# PCB_DYBoard_Bandmaster_V2_SCH4.net
KiCad netlist of a schematic drawn in Altium Designer
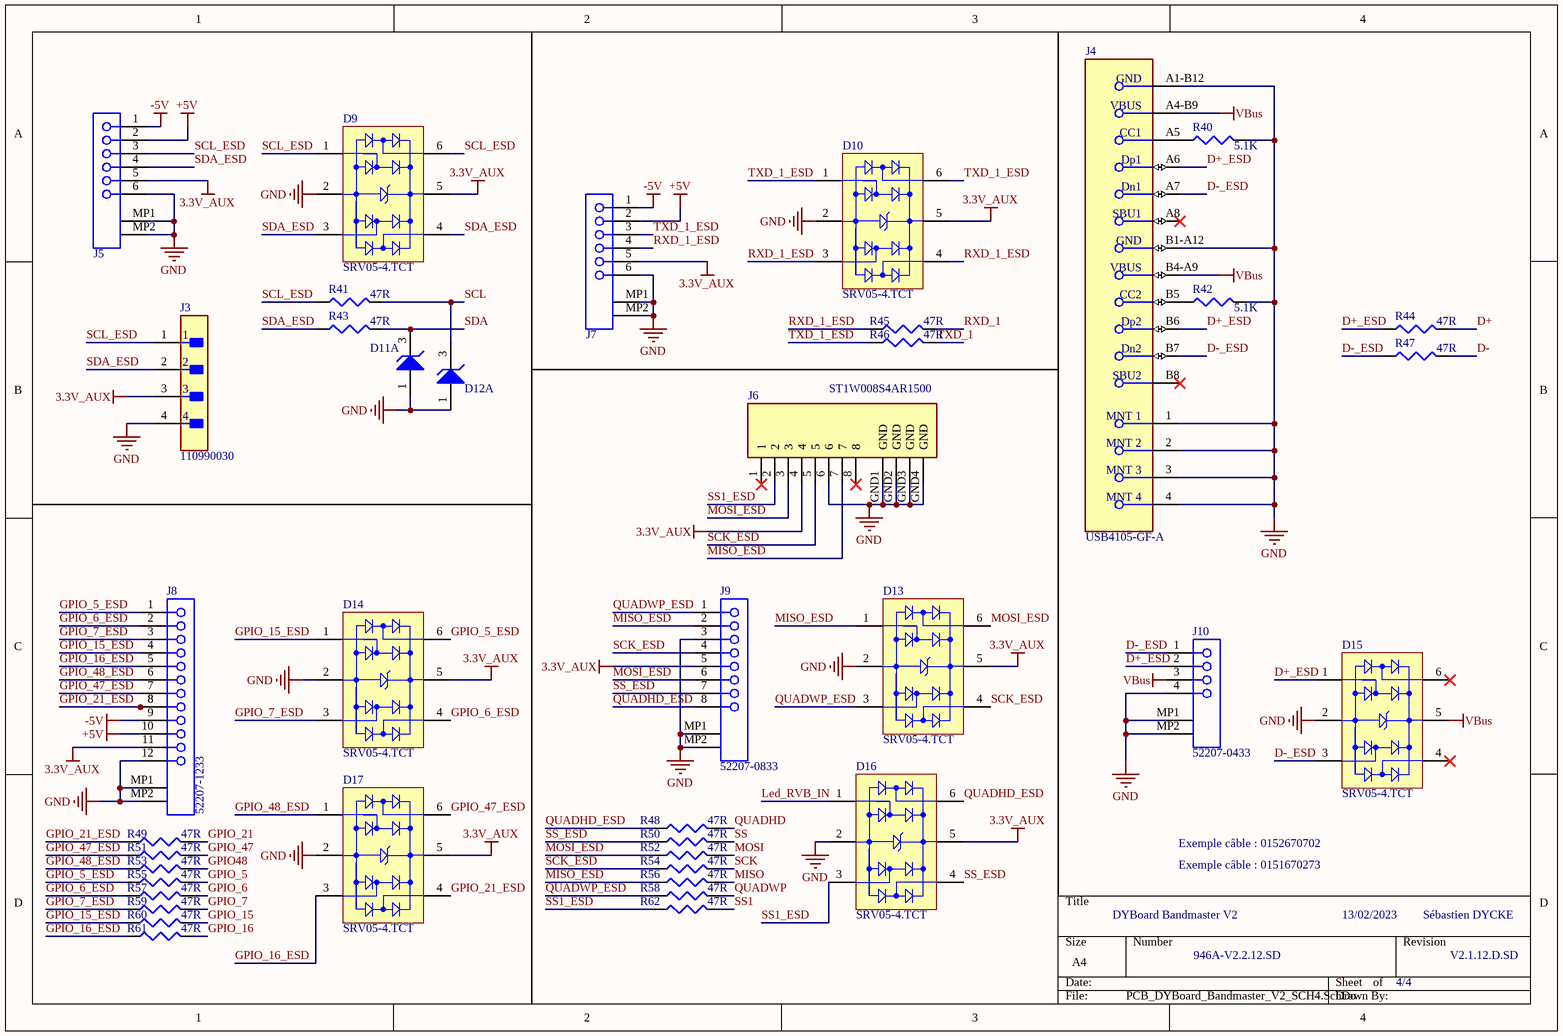
[diagram p0: PCB_DYBoard_Bandmaster_V2_SCH4.SchDoc]

(export (version "E")
  (design (tool "Eeschema 10.0.6"))
  (components
    (comp (ref "D9")
      (value "SRV05-4.TCT")
      (footprint "SMTC-SOT23-6_V")
      (fields (field (name "MANUFACTURER") "Semtech"))
      (libsource (lib "Altium Content Vault") (part "STM-USB_DVI_HDMIULC6-4SC6X-SOT23-6L"))
    )
    (comp (ref "D10")
      (value "SRV05-4.TCT")
      (footprint "SMTC-SOT23-6_V")
      (fields (field (name "MANUFACTURER") "Semtech"))
      (libsource (lib "Altium Content Vault") (part "STM-USB_DVI_HDMIULC6-4SC6X-SOT23-6L"))
    )
    (comp (ref "D11")
      (value "BZX84C3V9LT1G")
      (footprint "ONSC-SOT-23-3-318-08_V")
      (description "Zener Voltage Regulator, 225 mW, 3-Pin SOT-23, Pb-Free, Tape and Reel")
      (fields (field (name "MANUFACTURER") "On Semiconductor"))
      (libsource (lib "Altium Content Vault") (part "ONSC-A1K3-3"))
    )
    (comp (ref "D12")
      (value "BZX84C3V9LT1G")
      (footprint "ONSC-SOT-23-3-318-08_V")
      (description "Zener Voltage Regulator, 225 mW, 3-Pin SOT-23, Pb-Free, Tape and Reel")
      (fields (field (name "MANUFACTURER") "On Semiconductor"))
      (libsource (lib "Altium Content Vault") (part "ONSC-A1K3-3"))
    )
    (comp (ref "D13")
      (value "SRV05-4.TCT")
      (footprint "SMTC-SOT23-6_V")
      (fields (field (name "MANUFACTURER") "Semtech"))
      (libsource (lib "Altium Content Vault") (part "STM-USB_DVI_HDMIULC6-4SC6X-SOT23-6L"))
    )
    (comp (ref "D14")
      (value "SRV05-4.TCT")
      (footprint "SMTC-SOT23-6_V")
      (fields (field (name "MANUFACTURER") "Semtech"))
      (libsource (lib "Altium Content Vault") (part "STM-USB_DVI_HDMIULC6-4SC6X-SOT23-6L"))
    )
    (comp (ref "D15")
      (value "SRV05-4.TCT")
      (footprint "SMTC-SOT23-6_V")
      (fields (field (name "MANUFACTURER") "Semtech"))
      (libsource (lib "Altium Content Vault") (part "STM-USB_DVI_HDMIULC6-4SC6X-SOT23-6L"))
    )
    (comp (ref "D16")
      (value "SRV05-4.TCT")
      (footprint "SMTC-SOT23-6_V")
      (fields (field (name "MANUFACTURER") "Semtech"))
      (libsource (lib "Altium Content Vault") (part "STM-USB_DVI_HDMIULC6-4SC6X-SOT23-6L"))
    )
    (comp (ref "D17")
      (value "SRV05-4.TCT")
      (footprint "SMTC-SOT23-6_V")
      (fields (field (name "MANUFACTURER") "Semtech"))
      (libsource (lib "Altium Content Vault") (part "STM-USB_DVI_HDMIULC6-4SC6X-SOT23-6L"))
    )
    (comp (ref "J3")
      (value "110990030")
      (footprint "FP-110990030-MFG")
      (description "GROVE 2MM 4PIN VERT CONN 10PCS")
      (libsource (lib "Altium Content Vault") (part "299a8cea1bdcbc3624fe62c390fa72c"))
    )
    (comp (ref "J4")
      (value "USB4105-GF-A")
      (footprint "FP-USB4105-GF-A-MFG")
      (description "CONN RCPT USB2.0 TYPEC 5A")
      (fields
        (field (name "MANUFACTURER") "GCT")
        (field (name "OCTOPART") "https://octopart.com/usb4105-gf-a-gct-106627878")
      )
      (libsource (lib "Altium Content Vault") (part "e7c17a616881a82b79941196b4bec10"))
    )
    (comp (ref "J5")
      (value "SEB_MOLeX_6p")
      (footprint "SEB_MOLeX_6p")
      (libsource (lib "Lib_Altium_Sebastien_DYCKE") (part "SEB_MOLeX_6p"))
    )
    (comp (ref "J6")
      (value "ST1W008S4AR1500")
      (footprint "JAE_ST1W008S4AR1500")
      (description "8 Position Card Connector Secure Digital - microSDâ„¢ Surface Mount, Right Angle Gold")
      (fields (field (name "MF") "JAE Electronics"))
      (libsource (lib "ST1W008S4AR1500") (part "ST1W008S4AR1500"))
    )
    (comp (ref "J7")
      (value "SEB_MOLeX_6p")
      (footprint "SEB_MOLeX_6p")
      (libsource (lib "Lib_Altium_Sebastien_DYCKE") (part "SEB_MOLeX_6p"))
    )
    (comp (ref "J8")
      (value "52207-1233")
      (footprint "52207-1233")
      (libsource (lib "Lib_Altium_Sebastien_DYCKE") (part "52207-1233"))
    )
    (comp (ref "J9")
      (value "52207-0833")
      (footprint "con_molex_8_52207-0833")
      (libsource (lib "Lib_Altium_Sebastien_DYCKE") (part "52207-0833"))
    )
    (comp (ref "J10")
      (value "52207-0433")
      (footprint "52207-0433")
      (libsource (lib "Lib_Altium_Sebastien_DYCKE") (part "52207-0433"))
    )
    (comp (ref "R40")
      (value "5.1K")
      (footprint "J1-0603")
      (description "Resistor")
      (fields (field (name "Comment") "Res3") (field (name "PUBLISHER") "Altium Limited"))
      (libsource (lib "Miscellaneous Devices") (part "Res3"))
    )
    (comp (ref "R41")
      (value "47R")
      (footprint "J1-0603")
      (description "Resistor")
      (fields (field (name "Comment") "Res3") (field (name "PUBLISHER") "Altium Limited"))
      (libsource (lib "Miscellaneous Devices") (part "Res3"))
    )
    (comp (ref "R42")
      (value "5.1K")
      (footprint "J1-0603")
      (description "Resistor")
      (fields (field (name "Comment") "Res3") (field (name "PUBLISHER") "Altium Limited"))
      (libsource (lib "Miscellaneous Devices") (part "Res3"))
    )
    (comp (ref "R43")
      (value "47R")
      (footprint "J1-0603")
      (description "Resistor")
      (fields (field (name "Comment") "Res3") (field (name "PUBLISHER") "Altium Limited"))
      (libsource (lib "Miscellaneous Devices") (part "Res3"))
    )
    (comp (ref "R44")
      (value "47R")
      (footprint "J1-0603")
      (description "Resistor")
      (fields (field (name "Comment") "Res3") (field (name "PUBLISHER") "Altium Limited"))
      (libsource (lib "Miscellaneous Devices") (part "Res3"))
    )
    (comp (ref "R45")
      (value "47R")
      (footprint "J1-0603")
      (description "Resistor")
      (fields (field (name "Comment") "Res3") (field (name "PUBLISHER") "Altium Limited"))
      (libsource (lib "Miscellaneous Devices") (part "Res3"))
    )
    (comp (ref "R46")
      (value "47R")
      (footprint "J1-0603")
      (description "Resistor")
      (fields (field (name "Comment") "Res3") (field (name "PUBLISHER") "Altium Limited"))
      (libsource (lib "Miscellaneous Devices") (part "Res3"))
    )
    (comp (ref "R47")
      (value "47R")
      (footprint "J1-0603")
      (description "Resistor")
      (fields (field (name "Comment") "Res3") (field (name "PUBLISHER") "Altium Limited"))
      (libsource (lib "Miscellaneous Devices") (part "Res3"))
    )
    (comp (ref "R48")
      (value "47R")
      (footprint "J1-0603")
      (description "Resistor")
      (fields (field (name "Comment") "Res3") (field (name "PUBLISHER") "Altium Limited"))
      (libsource (lib "Miscellaneous Devices") (part "Res3"))
    )
    (comp (ref "R49")
      (value "47R")
      (footprint "J1-0603")
      (description "Resistor")
      (fields (field (name "Comment") "Res3") (field (name "PUBLISHER") "Altium Limited"))
      (libsource (lib "Miscellaneous Devices") (part "Res3"))
    )
    (comp (ref "R50")
      (value "47R")
      (footprint "J1-0603")
      (description "Resistor")
      (fields (field (name "Comment") "Res3") (field (name "PUBLISHER") "Altium Limited"))
      (libsource (lib "Miscellaneous Devices") (part "Res3"))
    )
    (comp (ref "R51")
      (value "47R")
      (footprint "J1-0603")
      (description "Resistor")
      (fields (field (name "Comment") "Res3") (field (name "PUBLISHER") "Altium Limited"))
      (libsource (lib "Miscellaneous Devices") (part "Res3"))
    )
    (comp (ref "R52")
      (value "47R")
      (footprint "J1-0603")
      (description "Resistor")
      (fields (field (name "Comment") "Res3") (field (name "PUBLISHER") "Altium Limited"))
      (libsource (lib "Miscellaneous Devices") (part "Res3"))
    )
    (comp (ref "R53")
      (value "47R")
      (footprint "J1-0603")
      (description "Resistor")
      (fields (field (name "Comment") "Res3") (field (name "PUBLISHER") "Altium Limited"))
      (libsource (lib "Miscellaneous Devices") (part "Res3"))
    )
    (comp (ref "R54")
      (value "47R")
      (footprint "J1-0603")
      (description "Resistor")
      (fields (field (name "Comment") "Res3") (field (name "PUBLISHER") "Altium Limited"))
      (libsource (lib "Miscellaneous Devices") (part "Res3"))
    )
    (comp (ref "R55")
      (value "47R")
      (footprint "J1-0603")
      (description "Resistor")
      (fields (field (name "Comment") "Res3") (field (name "PUBLISHER") "Altium Limited"))
      (libsource (lib "Miscellaneous Devices") (part "Res3"))
    )
    (comp (ref "R56")
      (value "47R")
      (footprint "J1-0603")
      (description "Resistor")
      (fields (field (name "Comment") "Res3") (field (name "PUBLISHER") "Altium Limited"))
      (libsource (lib "Miscellaneous Devices") (part "Res3"))
    )
    (comp (ref "R57")
      (value "47R")
      (footprint "J1-0603")
      (description "Resistor")
      (fields (field (name "Comment") "Res3") (field (name "PUBLISHER") "Altium Limited"))
      (libsource (lib "Miscellaneous Devices") (part "Res3"))
    )
    (comp (ref "R58")
      (value "47R")
      (footprint "J1-0603")
      (description "Resistor")
      (fields (field (name "Comment") "Res3") (field (name "PUBLISHER") "Altium Limited"))
      (libsource (lib "Miscellaneous Devices") (part "Res3"))
    )
    (comp (ref "R59")
      (value "47R")
      (footprint "J1-0603")
      (description "Resistor")
      (fields (field (name "Comment") "Res3") (field (name "PUBLISHER") "Altium Limited"))
      (libsource (lib "Miscellaneous Devices") (part "Res3"))
    )
    (comp (ref "R60")
      (value "47R")
      (footprint "J1-0603")
      (description "Resistor")
      (fields (field (name "Comment") "Res3") (field (name "PUBLISHER") "Altium Limited"))
      (libsource (lib "Miscellaneous Devices") (part "Res3"))
    )
    (comp (ref "R61")
      (value "47R")
      (footprint "J1-0603")
      (description "Resistor")
      (fields (field (name "Comment") "Res3") (field (name "PUBLISHER") "Altium Limited"))
      (libsource (lib "Miscellaneous Devices") (part "Res3"))
    )
    (comp (ref "R62")
      (value "47R")
      (footprint "J1-0603")
      (description "Resistor")
      (fields (field (name "Comment") "Res3") (field (name "PUBLISHER") "Altium Limited"))
      (libsource (lib "Miscellaneous Devices") (part "Res3"))
    )
  )
  (nets
    (net (code "1") (name "+5V") (class "Default")
      (node (ref "J5") (pin "2") (pinfunction "2_2") (pintype "passive"))
      (node (ref "J7") (pin "2") (pinfunction "2_2") (pintype "passive"))
      (node (ref "J8") (pin "10") (pinfunction "10_10") (pintype "passive"))
    )
    (net (code "2") (name "-5V") (class "Default")
      (node (ref "J5") (pin "1") (pinfunction "1_1") (pintype "passive"))
      (node (ref "J7") (pin "1") (pinfunction "1_1") (pintype "passive"))
      (node (ref "J8") (pin "9") (pinfunction "9_9") (pintype "passive"))
    )
    (net (code "3") (name "/D+") (class "Default")
      (node (ref "R44") (pin "2") (pinfunction "2_2") (pintype "passive"))
    )
    (net (code "4") (name "/D+_ESD") (class "Default")
      (node (ref "D15") (pin "1") (pinfunction "I/O_1_1") (pintype "passive"))
      (node (ref "J10") (pin "2") (pinfunction "2_2") (pintype "passive"))
      (node (ref "J4") (pin "A6") (pinfunction "Dp1_A6") (pintype "bidirectional"))
      (node (ref "J4") (pin "B6") (pinfunction "Dp2_B6") (pintype "bidirectional"))
      (node (ref "R44") (pin "1") (pinfunction "1_1") (pintype "passive"))
    )
    (net (code "5") (name "/D-") (class "Default")
      (node (ref "R47") (pin "2") (pinfunction "2_2") (pintype "passive"))
    )
    (net (code "6") (name "/D-_ESD") (class "Default")
      (node (ref "D15") (pin "3") (pinfunction "I/O_2_3") (pintype "passive"))
      (node (ref "J10") (pin "1") (pinfunction "1_1") (pintype "passive"))
      (node (ref "J4") (pin "A7") (pinfunction "Dn1_A7") (pintype "bidirectional"))
      (node (ref "J4") (pin "B7") (pinfunction "Dn2_B7") (pintype "bidirectional"))
      (node (ref "R47") (pin "1") (pinfunction "1_1") (pintype "passive"))
    )
    (net (code "7") (name "/GPIO48") (class "Default")
      (node (ref "R53") (pin "2") (pinfunction "2_2") (pintype "passive"))
    )
    (net (code "8") (name "/GPIO_5") (class "Default")
      (node (ref "R55") (pin "2") (pinfunction "2_2") (pintype "passive"))
    )
    (net (code "9") (name "/GPIO_5_ESD") (class "Default")
      (node (ref "D14") (pin "6") (pinfunction "I/O_4_6") (pintype "passive"))
      (node (ref "J8") (pin "1") (pinfunction "1_1") (pintype "passive"))
      (node (ref "R55") (pin "1") (pinfunction "1_1") (pintype "passive"))
    )
    (net (code "10") (name "/GPIO_6") (class "Default")
      (node (ref "R57") (pin "2") (pinfunction "2_2") (pintype "passive"))
    )
    (net (code "11") (name "/GPIO_6_ESD") (class "Default")
      (node (ref "D14") (pin "4") (pinfunction "I/O_3_4") (pintype "passive"))
      (node (ref "J8") (pin "2") (pinfunction "2_2") (pintype "passive"))
      (node (ref "R57") (pin "1") (pinfunction "1_1") (pintype "passive"))
    )
    (net (code "12") (name "/GPIO_7") (class "Default")
      (node (ref "R59") (pin "2") (pinfunction "2_2") (pintype "passive"))
    )
    (net (code "13") (name "/GPIO_7_ESD") (class "Default")
      (node (ref "D14") (pin "3") (pinfunction "I/O_2_3") (pintype "passive"))
      (node (ref "J8") (pin "3") (pinfunction "3_3") (pintype "passive"))
      (node (ref "R59") (pin "1") (pinfunction "1_1") (pintype "passive"))
    )
    (net (code "14") (name "/GPIO_15") (class "Default")
      (node (ref "R60") (pin "2") (pinfunction "2_2") (pintype "passive"))
    )
    (net (code "15") (name "/GPIO_15_ESD") (class "Default")
      (node (ref "D14") (pin "1") (pinfunction "I/O_1_1") (pintype "passive"))
      (node (ref "J8") (pin "4") (pinfunction "4_4") (pintype "passive"))
      (node (ref "R60") (pin "1") (pinfunction "1_1") (pintype "passive"))
    )
    (net (code "16") (name "/GPIO_16") (class "Default")
      (node (ref "R61") (pin "2") (pinfunction "2_2") (pintype "passive"))
    )
    (net (code "17") (name "/GPIO_16_ESD") (class "Default")
      (node (ref "D17") (pin "3") (pinfunction "I/O_2_3") (pintype "passive"))
      (node (ref "J8") (pin "5") (pinfunction "5_5") (pintype "passive"))
      (node (ref "R61") (pin "1") (pinfunction "1_1") (pintype "passive"))
    )
    (net (code "18") (name "/GPIO_21") (class "Default")
      (node (ref "R49") (pin "2") (pinfunction "2_2") (pintype "passive"))
    )
    (net (code "19") (name "/GPIO_21_ESD") (class "Default")
      (node (ref "D17") (pin "4") (pinfunction "I/O_3_4") (pintype "passive"))
      (node (ref "J8") (pin "8") (pinfunction "8_8") (pintype "passive"))
      (node (ref "R49") (pin "1") (pinfunction "1_1") (pintype "passive"))
    )
    (net (code "20") (name "/GPIO_47") (class "Default")
      (node (ref "R51") (pin "2") (pinfunction "2_2") (pintype "passive"))
    )
    (net (code "21") (name "/GPIO_47_ESD") (class "Default")
      (node (ref "D17") (pin "6") (pinfunction "I/O_4_6") (pintype "passive"))
      (node (ref "J8") (pin "7") (pinfunction "7_7") (pintype "passive"))
      (node (ref "R51") (pin "1") (pinfunction "1_1") (pintype "passive"))
    )
    (net (code "22") (name "/GPIO_48_ESD") (class "Default")
      (node (ref "D17") (pin "1") (pinfunction "I/O_1_1") (pintype "passive"))
      (node (ref "J8") (pin "6") (pinfunction "6_6") (pintype "passive"))
      (node (ref "R53") (pin "1") (pinfunction "1_1") (pintype "passive"))
    )
    (net (code "23") (name "/Led_RVB_IN") (class "Default")
      (node (ref "D16") (pin "1") (pinfunction "I/O_1_1") (pintype "passive"))
    )
    (net (code "24") (name "/MISO") (class "Default")
      (node (ref "R56") (pin "2") (pinfunction "2_2") (pintype "passive"))
    )
    (net (code "25") (name "/MISO_ESD") (class "Default")
      (node (ref "D13") (pin "1") (pinfunction "I/O_1_1") (pintype "passive"))
      (node (ref "J6") (pin "7") (pinfunction "7_7") (pintype "passive"))
      (node (ref "J9") (pin "2") (pinfunction "2_2") (pintype "passive"))
      (node (ref "R56") (pin "1") (pinfunction "1_1") (pintype "passive"))
    )
    (net (code "26") (name "/MOSI") (class "Default")
      (node (ref "R52") (pin "2") (pinfunction "2_2") (pintype "passive"))
    )
    (net (code "27") (name "/MOSI_ESD") (class "Default")
      (node (ref "D13") (pin "6") (pinfunction "I/O_4_6") (pintype "passive"))
      (node (ref "J6") (pin "3") (pinfunction "3_3") (pintype "passive"))
      (node (ref "J9") (pin "6") (pinfunction "6_6") (pintype "passive"))
      (node (ref "R52") (pin "1") (pinfunction "1_1") (pintype "passive"))
    )
    (net (code "28") (name "/QUADHD") (class "Default")
      (node (ref "R48") (pin "2") (pinfunction "2_2") (pintype "passive"))
    )
    (net (code "29") (name "/QUADHD_ESD") (class "Default")
      (node (ref "D16") (pin "6") (pinfunction "I/O_4_6") (pintype "passive"))
      (node (ref "J9") (pin "8") (pinfunction "8_8") (pintype "passive"))
      (node (ref "R48") (pin "1") (pinfunction "1_1") (pintype "passive"))
    )
    (net (code "30") (name "/QUADWP") (class "Default")
      (node (ref "R58") (pin "2") (pinfunction "2_2") (pintype "passive"))
    )
    (net (code "31") (name "/QUADWP_ESD") (class "Default")
      (node (ref "D13") (pin "3") (pinfunction "I/O_2_3") (pintype "passive"))
      (node (ref "J9") (pin "1") (pinfunction "1_1") (pintype "passive"))
      (node (ref "R58") (pin "1") (pinfunction "1_1") (pintype "passive"))
    )
    (net (code "32") (name "/RXD_1") (class "Default")
      (node (ref "R45") (pin "2") (pinfunction "2_2") (pintype "passive"))
    )
    (net (code "33") (name "/RXD_1_ESD") (class "Default")
      (node (ref "D10") (pin "3") (pinfunction "I/O_2_3") (pintype "passive"))
      (node (ref "D10") (pin "4") (pinfunction "I/O_3_4") (pintype "passive"))
      (node (ref "J7") (pin "4") (pinfunction "4_4") (pintype "passive"))
      (node (ref "R45") (pin "1") (pinfunction "1_1") (pintype "passive"))
    )
    (net (code "34") (name "/SCK") (class "Default")
      (node (ref "R54") (pin "2") (pinfunction "2_2") (pintype "passive"))
    )
    (net (code "35") (name "/SCK_ESD") (class "Default")
      (node (ref "D13") (pin "4") (pinfunction "I/O_3_4") (pintype "passive"))
      (node (ref "J6") (pin "5") (pinfunction "5_5") (pintype "passive"))
      (node (ref "J9") (pin "4") (pinfunction "4_4") (pintype "passive"))
      (node (ref "R54") (pin "1") (pinfunction "1_1") (pintype "passive"))
    )
    (net (code "36") (name "/SCL") (class "Default")
      (node (ref "D12") (pin "3") (pinfunction "K_3") (pintype "passive"))
      (node (ref "R41") (pin "2") (pinfunction "2_2") (pintype "passive"))
    )
    (net (code "37") (name "/SCL_ESD") (class "Default")
      (node (ref "D9") (pin "1") (pinfunction "I/O_1_1") (pintype "passive"))
      (node (ref "D9") (pin "6") (pinfunction "I/O_4_6") (pintype "passive"))
      (node (ref "J3") (pin "1") (pinfunction "1_1") (pintype "passive"))
      (node (ref "J5") (pin "3") (pinfunction "3_3") (pintype "passive"))
      (node (ref "R41") (pin "1") (pinfunction "1_1") (pintype "passive"))
    )
    (net (code "38") (name "/SDA") (class "Default")
      (node (ref "D11") (pin "3") (pinfunction "K_3") (pintype "passive"))
      (node (ref "R43") (pin "2") (pinfunction "2_2") (pintype "passive"))
    )
    (net (code "39") (name "/SDA_ESD") (class "Default")
      (node (ref "D9") (pin "3") (pinfunction "I/O_2_3") (pintype "passive"))
      (node (ref "D9") (pin "4") (pinfunction "I/O_3_4") (pintype "passive"))
      (node (ref "J3") (pin "2") (pinfunction "2_2") (pintype "passive"))
      (node (ref "J5") (pin "4") (pinfunction "4_4") (pintype "passive"))
      (node (ref "R43") (pin "1") (pinfunction "1_1") (pintype "passive"))
    )
    (net (code "40") (name "/SS") (class "Default")
      (node (ref "R50") (pin "2") (pinfunction "2_2") (pintype "passive"))
    )
    (net (code "41") (name "/SS1") (class "Default")
      (node (ref "R62") (pin "2") (pinfunction "2_2") (pintype "passive"))
    )
    (net (code "42") (name "/SS1_ESD") (class "Default")
      (node (ref "D16") (pin "3") (pinfunction "I/O_2_3") (pintype "passive"))
      (node (ref "J6") (pin "2") (pinfunction "2_2") (pintype "passive"))
      (node (ref "R62") (pin "1") (pinfunction "1_1") (pintype "passive"))
    )
    (net (code "43") (name "/SS_ESD") (class "Default")
      (node (ref "D16") (pin "4") (pinfunction "I/O_3_4") (pintype "passive"))
      (node (ref "J9") (pin "7") (pinfunction "7_7") (pintype "passive"))
      (node (ref "R50") (pin "1") (pinfunction "1_1") (pintype "passive"))
    )
    (net (code "44") (name "/TXD_1") (class "Default")
      (node (ref "R46") (pin "2") (pinfunction "2_2") (pintype "passive"))
    )
    (net (code "45") (name "/TXD_1_ESD") (class "Default")
      (node (ref "D10") (pin "1") (pinfunction "I/O_1_1") (pintype "passive"))
      (node (ref "D10") (pin "6") (pinfunction "I/O_4_6") (pintype "passive"))
      (node (ref "J7") (pin "3") (pinfunction "3_3") (pintype "passive"))
      (node (ref "R46") (pin "1") (pinfunction "1_1") (pintype "passive"))
    )
    (net (code "46") (name "3.3V_AUX") (class "Default")
      (node (ref "D10") (pin "5") (pinfunction "VBUS_5") (pintype "passive"))
      (node (ref "D13") (pin "5") (pinfunction "VBUS_5") (pintype "passive"))
      (node (ref "D14") (pin "5") (pinfunction "VBUS_5") (pintype "passive"))
      (node (ref "D16") (pin "5") (pinfunction "VBUS_5") (pintype "passive"))
      (node (ref "D17") (pin "5") (pinfunction "VBUS_5") (pintype "passive"))
      (node (ref "D9") (pin "5") (pinfunction "VBUS_5") (pintype "passive"))
      (node (ref "J3") (pin "3") (pinfunction "3_3") (pintype "passive"))
      (node (ref "J5") (pin "5") (pinfunction "5_5") (pintype "passive"))
      (node (ref "J6") (pin "4") (pinfunction "4_4") (pintype "passive"))
      (node (ref "J7") (pin "5") (pinfunction "5_5") (pintype "passive"))
      (node (ref "J8") (pin "11") (pinfunction "11_11") (pintype "passive"))
      (node (ref "J9") (pin "5") (pinfunction "5_5") (pintype "passive"))
    )
    (net (code "47") (name "GND") (class "Default")
      (node (ref "D10") (pin "2") (pinfunction "GND_2") (pintype "passive"))
      (node (ref "D11") (pin "1") (pinfunction "A_1") (pintype "passive"))
      (node (ref "D12") (pin "1") (pinfunction "A_1") (pintype "passive"))
      (node (ref "D13") (pin "2") (pinfunction "GND_2") (pintype "passive"))
      (node (ref "D14") (pin "2") (pinfunction "GND_2") (pintype "passive"))
      (node (ref "D15") (pin "2") (pinfunction "GND_2") (pintype "passive"))
      (node (ref "D16") (pin "2") (pinfunction "GND_2") (pintype "passive"))
      (node (ref "D17") (pin "2") (pinfunction "GND_2") (pintype "passive"))
      (node (ref "D9") (pin "2") (pinfunction "GND_2") (pintype "passive"))
      (node (ref "J10") (pin "4") (pinfunction "4_4") (pintype "passive"))
      (node (ref "J10") (pin "MP1") (pinfunction "MP1_MP1") (pintype "passive"))
      (node (ref "J10") (pin "MP2") (pinfunction "MP2_MP2") (pintype "passive"))
      (node (ref "J3") (pin "4") (pinfunction "4_4") (pintype "passive"))
      (node (ref "J4") (pin "1") (pinfunction "MNT_1_1") (pintype "power_in"))
      (node (ref "J4") (pin "2") (pinfunction "MNT_2_2") (pintype "power_in"))
      (node (ref "J4") (pin "3") (pinfunction "MNT_3_3") (pintype "power_in"))
      (node (ref "J4") (pin "4") (pinfunction "MNT_4_4") (pintype "power_in"))
      (node (ref "J4") (pin "A1-B12") (pinfunction "GND_A1-B12") (pintype "power_in"))
      (node (ref "J4") (pin "B1-A12") (pinfunction "GND_B1-A12") (pintype "bidirectional"))
      (node (ref "J5") (pin "6") (pinfunction "6_6") (pintype "passive"))
      (node (ref "J5") (pin "MP1") (pinfunction "MP1_MP1") (pintype "passive"))
      (node (ref "J5") (pin "MP2") (pinfunction "MP2_MP2") (pintype "passive"))
      (node (ref "J6") (pin "6") (pinfunction "6_6") (pintype "passive"))
      (node (ref "J6") (pin "GND1") (pinfunction "GND_GND1") (pintype "power_in"))
      (node (ref "J6") (pin "GND2") (pinfunction "GND_GND2") (pintype "power_in"))
      (node (ref "J6") (pin "GND3") (pinfunction "GND_GND3") (pintype "power_in"))
      (node (ref "J6") (pin "GND4") (pinfunction "GND_GND4") (pintype "power_in"))
      (node (ref "J7") (pin "6") (pinfunction "6_6") (pintype "passive"))
      (node (ref "J7") (pin "MP1") (pinfunction "MP1_MP1") (pintype "passive"))
      (node (ref "J7") (pin "MP2") (pinfunction "MP2_MP2") (pintype "passive"))
      (node (ref "J8") (pin "12") (pinfunction "12_12") (pintype "passive"))
      (node (ref "J8") (pin "MP1") (pinfunction "MP1_MP1") (pintype "passive"))
      (node (ref "J8") (pin "MP2") (pinfunction "MP2_MP2") (pintype "passive"))
      (node (ref "J9") (pin "3") (pinfunction "3_3") (pintype "passive"))
      (node (ref "J9") (pin "MP1") (pinfunction "MP1_MP1") (pintype "passive"))
      (node (ref "J9") (pin "MP2") (pinfunction "MP2_MP2") (pintype "passive"))
      (node (ref "R40") (pin "2") (pinfunction "2_2") (pintype "passive"))
      (node (ref "R42") (pin "2") (pinfunction "2_2") (pintype "passive"))
    )
    (net (code "48") (name "Net-(J4-CC1)") (class "Default")
      (node (ref "J4") (pin "A5") (pinfunction "CC1_A5") (pintype "power_in"))
      (node (ref "R40") (pin "1") (pinfunction "1_1") (pintype "passive"))
    )
    (net (code "49") (name "Net-(J4-CC2)") (class "Default")
      (node (ref "J4") (pin "B5") (pinfunction "CC2_B5") (pintype "bidirectional"))
      (node (ref "R42") (pin "1") (pinfunction "1_1") (pintype "passive"))
    )
    (net (code "50") (name "VBus") (class "Default")
      (node (ref "D15") (pin "5") (pinfunction "VBUS_5") (pintype "passive"))
      (node (ref "J10") (pin "3") (pinfunction "3_3") (pintype "passive"))
      (node (ref "J4") (pin "A4-B9") (pinfunction "VBUS_A4-B9") (pintype "power_in"))
      (node (ref "J4") (pin "B4-A9") (pinfunction "VBUS_B4-A9") (pintype "bidirectional"))
    )
    (net (code "51") (name "unconnected-(D15-I{slash}O_3-Pad4)") (class "Default")
      (node (ref "D15") (pin "4") (pinfunction "I/O_3_4") (pintype "passive+no_connect"))
    )
    (net (code "52") (name "unconnected-(D15-I{slash}O_4-Pad6)") (class "Default")
      (node (ref "D15") (pin "6") (pinfunction "I/O_4_6") (pintype "passive+no_connect"))
    )
    (net (code "53") (name "unconnected-(J4-SBU1-PadA8)") (class "Default")
      (node (ref "J4") (pin "A8") (pinfunction "SBU1_A8") (pintype "bidirectional+no_connect"))
    )
    (net (code "54") (name "unconnected-(J4-SBU2-PadB8)") (class "Default")
      (node (ref "J4") (pin "B8") (pinfunction "SBU2_B8") (pintype "power_in+no_connect"))
    )
    (net (code "55") (name "unconnected-(J6-Pad1)") (class "Default")
      (node (ref "J6") (pin "1") (pinfunction "1_1") (pintype "passive+no_connect"))
    )
    (net (code "56") (name "unconnected-(J6-Pad8)") (class "Default")
      (node (ref "J6") (pin "8") (pinfunction "8_8") (pintype "passive+no_connect"))
    )
  )
)
